# Light_node.net
KiCad netlist of a schematic drawn in EAGLE
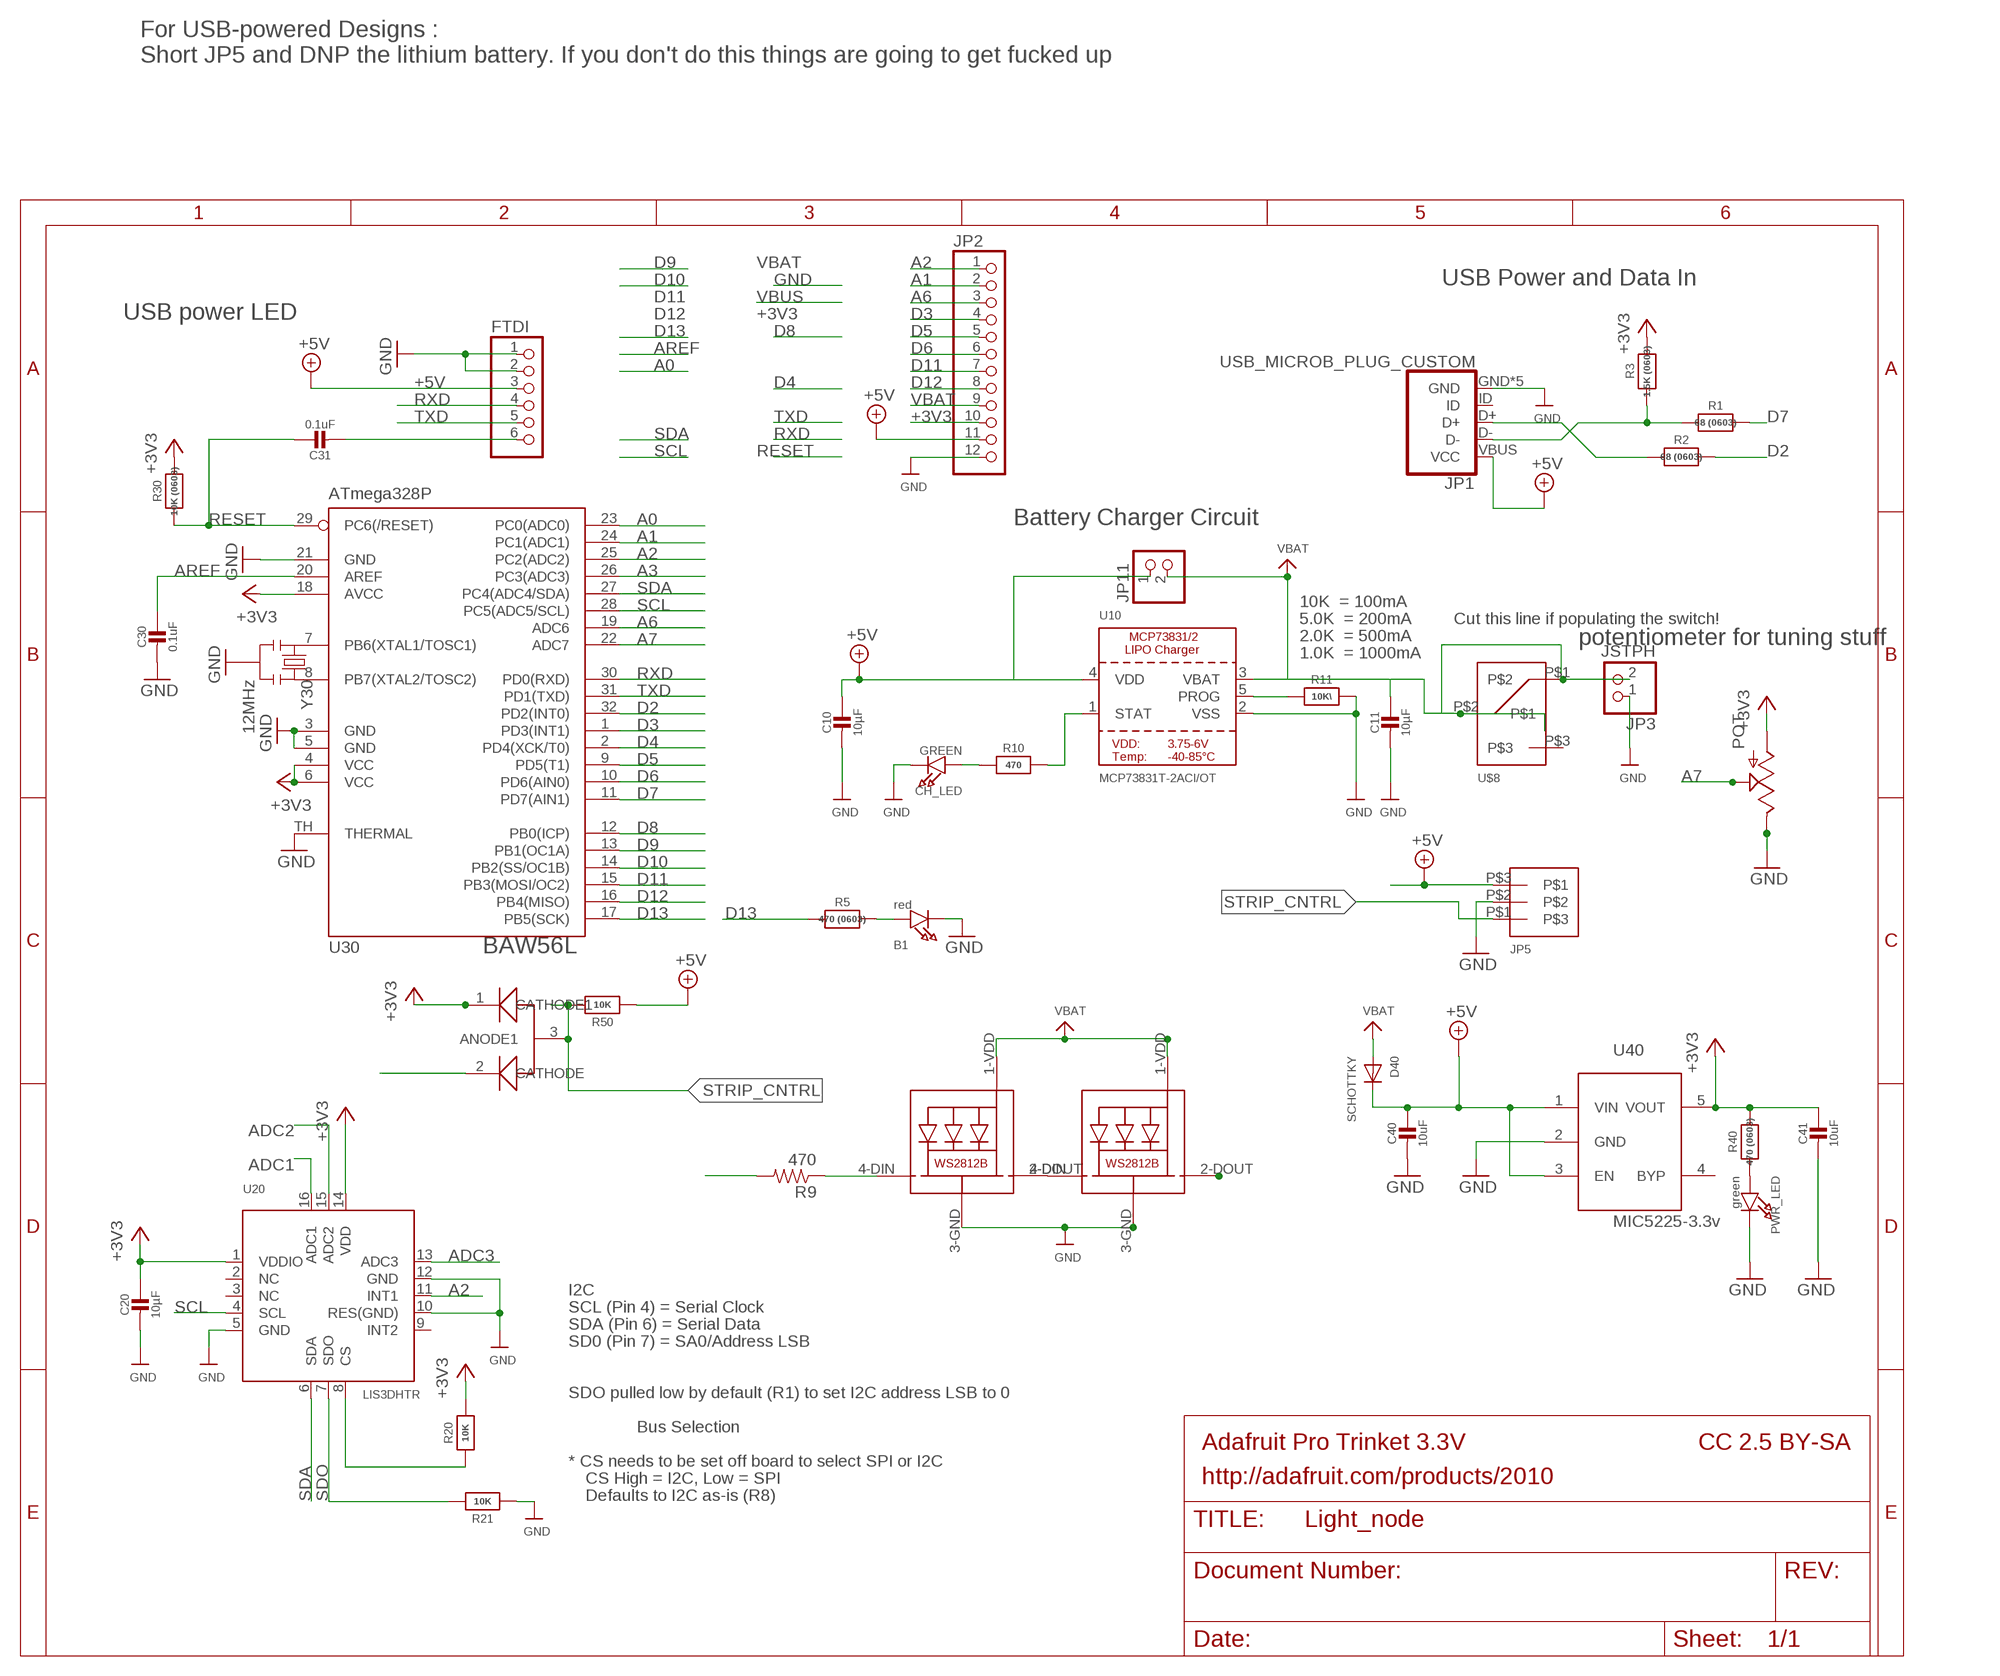
[diagram p0: schematic, sheet 1]

(export (version "E")
  (design (tool "Eeschema 10.0.6"))
  (components
    (comp (ref "B1")
      (value "red")
      (footprint "eagle-import:CHIPLED_0805_NOOUTLINE")
      (libsource (lib "eagle-import") (part "LED0805_NOOUTLINE"))
    )
    (comp (ref "C10")
      (value "10µF")
      (footprint "eagle-import:0805-NO")
      (libsource (lib "eagle-import") (part "CAP_CERAMIC0805-NOOUTLINE"))
    )
    (comp (ref "C11")
      (value "10µF")
      (footprint "eagle-import:0805-NO")
      (libsource (lib "eagle-import") (part "CAP_CERAMIC0805-NOOUTLINE"))
    )
    (comp (ref "C20")
      (value "10µF")
      (footprint "eagle-import:0805-NO")
      (libsource (lib "eagle-import") (part "CAP_CERAMIC0805-NOOUTLINE"))
    )
    (comp (ref "C30")
      (value "0.1uF")
      (footprint "eagle-import:_0805MP")
      (libsource (lib "eagle-import") (part "CAP_CERAMIC_0805MP"))
    )
    (comp (ref "C31")
      (value "0.1uF")
      (footprint "eagle-import:0805-NO")
      (libsource (lib "eagle-import") (part "CAP_CERAMIC0805-NOOUTLINE"))
    )
    (comp (ref "C40")
      (value "10uF")
      (footprint "eagle-import:0805-NO")
      (libsource (lib "eagle-import") (part "CAP_CERAMIC0805-NOOUTLINE"))
    )
    (comp (ref "C41")
      (value "10uF")
      (footprint "eagle-import:0805-NO")
      (libsource (lib "eagle-import") (part "CAP_CERAMIC0805-NOOUTLINE"))
    )
    (comp (ref "CH_LED")
      (value "GREEN")
      (footprint "eagle-import:CHIPLED_0805_NOOUTLINE")
      (libsource (lib "eagle-import") (part "LED0805_NOOUTLINE"))
    )
    (comp (ref "D40")
      (value "SCHOTTKY")
      (footprint "eagle-import:SOD-123FL")
      (libsource (lib "eagle-import") (part "DIODE_SOD-123FL"))
    )
    (comp (ref "FTDI")
      (value "PINHD-1X6CB")
      (footprint "eagle-import:1X06-CLEANBIG")
      (libsource (lib "eagle-import") (part "PINHD-1X6CB"))
    )
    (comp (ref "JP1")
      (value "USB_MICROB_PLUG_CUSTOM")
      (footprint "eagle-import:USB-MICROB")
      (libsource (lib "eagle-import") (part "USB_MICROB_PLUG_CUSTOM"))
    )
    (comp (ref "JP2")
      (value "PINHD-1X12-CB")
      (footprint "eagle-import:1X12-CB")
      (libsource (lib "eagle-import") (part "PINHD-1X12-CB"))
    )
    (comp (ref "JP3")
      (value "JSTPH")
      (footprint "eagle-import:JSTPH2")
      (libsource (lib "eagle-import") (part "JST_2PIN"))
    )
    (comp (ref "JP5")
      (value "M03")
      (footprint "eagle-import:M03_25MM")
      (libsource (lib "eagle-import") (part "M03"))
    )
    (comp (ref "JP11")
      (value "HEADER-1X2ROUND")
      (footprint "eagle-import:1X02_ROUND")
      (libsource (lib "eagle-import") (part "HEADER-1X2ROUND"))
    )
    (comp (ref "POT")
      (value "POT")
      (footprint "eagle-import:3306P_POT")
      (libsource (lib "eagle-import") (part "POT"))
    )
    (comp (ref "PWR_LED")
      (value "green")
      (footprint "eagle-import:CHIPLED_0805_NOOUTLINE")
      (libsource (lib "eagle-import") (part "LED0805_NOOUTLINE"))
    )
    (comp (ref "R1")
      (value "68 (0603)")
      (footprint "eagle-import:0603-NO")
      (libsource (lib "eagle-import") (part "RESISTOR_0603_NOOUT"))
    )
    (comp (ref "R2")
      (value "68 (0603)")
      (footprint "eagle-import:0603-NO")
      (libsource (lib "eagle-import") (part "RESISTOR_0603_NOOUT"))
    )
    (comp (ref "R3")
      (value "1.5K (0603)")
      (footprint "eagle-import:0603-NO")
      (libsource (lib "eagle-import") (part "RESISTOR_0603_NOOUT"))
    )
    (comp (ref "R5")
      (value "470 (0603)")
      (footprint "eagle-import:0603-NO")
      (libsource (lib "eagle-import") (part "RESISTOR_0603_NOOUT"))
    )
    (comp (ref "R9")
      (value "470")
      (footprint "eagle-import:0603-RES")
      (libsource (lib "eagle-import") (part "RESISTOR0603-RES"))
    )
    (comp (ref "R10")
      (value "470")
      (footprint "eagle-import:0805-NO")
      (libsource (lib "eagle-import") (part "RESISTOR0805_NOOUTLINE"))
    )
    (comp (ref "R11")
      (value "10K\\")
      (footprint "eagle-import:0805-NO")
      (libsource (lib "eagle-import") (part "RESISTOR0805_NOOUTLINE"))
    )
    (comp (ref "R20")
      (value "10K")
      (footprint "eagle-import:0805-NO")
      (libsource (lib "eagle-import") (part "RESISTOR0805_NOOUTLINE"))
    )
    (comp (ref "R21")
      (value "10K")
      (footprint "eagle-import:0805-NO")
      (libsource (lib "eagle-import") (part "RESISTOR0805_NOOUTLINE"))
    )
    (comp (ref "R30")
      (value "10K (0603)")
      (footprint "eagle-import:0805-NO")
      (libsource (lib "eagle-import") (part "RESISTOR0805_NOOUTLINE"))
    )
    (comp (ref "R40")
      (value "470 (0603)")
      (footprint "eagle-import:0603-NO")
      (libsource (lib "eagle-import") (part "RESISTOR_0603_NOOUT"))
    )
    (comp (ref "R50")
      (value "10K")
      (footprint "eagle-import:0603-NO")
      (libsource (lib "eagle-import") (part "RESISTOR_0603_NOOUT"))
    )
    (comp (ref "RGB1")
      (value "WS2812B5050")
      (footprint "eagle-import:WS2812B")
      (libsource (lib "eagle-import") (part "WS2812B5050"))
    )
    (comp (ref "RGB2")
      (value "WS2812B5050")
      (footprint "eagle-import:WS2812B")
      (libsource (lib "eagle-import") (part "WS2812B5050"))
    )
    (comp (ref "U$8")
      (value "SPDT_NO_GNDSMT")
      (footprint "eagle-import:JS102011SAQN")
      (libsource (lib "eagle-import") (part "SPDT_NO_GNDSMT"))
    )
    (comp (ref "U10")
      (value "MCP73831T-2ACI/OT")
      (footprint "eagle-import:SOT23-5")
      (libsource (lib "eagle-import") (part "MCP73831/2"))
    )
    (comp (ref "U20")
      (value "LIS3DHTR")
      (footprint "eagle-import:LGA16_3X3MM")
      (libsource (lib "eagle-import") (part "ACCEL_LIS3DHTR"))
    )
    (comp (ref "U30")
      (value "ATmega328P")
      (footprint "eagle-import:MLF32-TH")
      (fields (field (name "MPN") "ATMEGA88PA-MU"))
      (libsource (lib "eagle-import") (part "MEGA8-MI"))
    )
    (comp (ref "U40")
      (value "MIC5225-3.3v")
      (footprint "eagle-import:SOT23-5L")
      (libsource (lib "eagle-import") (part "LP298XS"))
    )
    (comp (ref "U50")
      (value "COMMON_ANODE_DIODE")
      (footprint "eagle-import:SOT23")
      (libsource (lib "eagle-import") (part "COMMON_ANODE_DIODE"))
    )
    (comp (ref "Y30")
      (value "12MHz")
      (footprint "eagle-import:RESONATOR-SMD")
      (libsource (lib "eagle-import") (part "RESONATORSMD"))
    )
  )
  (nets
    (net (code "1") (name "+3V3") (class "Default")
      (node (ref "C20") (pin "1") (pinfunction "1_1") (pintype "passive"))
      (node (ref "C41") (pin "1") (pinfunction "1_1") (pintype "passive"))
      (node (ref "JP2") (pin "10") (pinfunction "10_10") (pintype "passive"))
      (node (ref "POT") (pin "P$1") (pinfunction "A_P$1") (pintype "passive"))
      (node (ref "R20") (pin "2") (pinfunction "2_2") (pintype "passive"))
      (node (ref "R3") (pin "2") (pinfunction "2_2") (pintype "passive"))
      (node (ref "R30") (pin "2") (pinfunction "2_2") (pintype "passive"))
      (node (ref "R40") (pin "2") (pinfunction "2_2") (pintype "passive"))
      (node (ref "U20") (pin "1") (pinfunction "VDDIO_1") (pintype "power_in"))
      (node (ref "U20") (pin "14") (pinfunction "VDD_14") (pintype "power_in"))
      (node (ref "U30") (pin "18") (pinfunction "AVCC_18") (pintype "power_in"))
      (node (ref "U30") (pin "4") (pinfunction "VCC_4") (pintype "power_in"))
      (node (ref "U30") (pin "6") (pinfunction "VCC_6") (pintype "power_in"))
      (node (ref "U40") (pin "5") (pinfunction "VOUT_5") (pintype "bidirectional"))
      (node (ref "U50") (pin "1") (pinfunction "CATHODE1_1") (pintype "bidirectional"))
    )
    (net (code "2") (name "+5V") (class "Default")
      (node (ref "C10") (pin "1") (pinfunction "1_1") (pintype "passive"))
      (node (ref "C40") (pin "1") (pinfunction "1_1") (pintype "passive"))
      (node (ref "D40") (pin "C") (pinfunction "C_C") (pintype "passive"))
      (node (ref "FTDI") (pin "3") (pinfunction "3_3") (pintype "passive"))
      (node (ref "JP1") (pin "VBUS") (pinfunction "VCC_VBUS") (pintype "bidirectional"))
      (node (ref "JP11") (pin "1") (pinfunction "1_1") (pintype "passive"))
      (node (ref "JP2") (pin "11") (pinfunction "11_11") (pintype "passive"))
      (node (ref "JP5") (pin "P$3") (pinfunction "P$1_P$3") (pintype "bidirectional"))
      (node (ref "R50") (pin "1") (pinfunction "1_1") (pintype "passive"))
      (node (ref "U10") (pin "4") (pinfunction "VDD_4") (pintype "power_in"))
      (node (ref "U40") (pin "1") (pinfunction "VIN_1") (pintype "bidirectional"))
      (node (ref "U40") (pin "3") (pinfunction "EN_3") (pintype "bidirectional"))
    )
    (net (code "3") (name "/A0") (class "Default")
      (node (ref "U30") (pin "23") (pinfunction "PC0(ADC0)_23") (pintype "bidirectional"))
    )
    (net (code "4") (name "/A1") (class "Default")
      (node (ref "JP2") (pin "2") (pinfunction "2_2") (pintype "passive"))
      (node (ref "U30") (pin "24") (pinfunction "PC1(ADC1)_24") (pintype "bidirectional"))
    )
    (net (code "5") (name "/A2") (class "Default")
      (node (ref "JP2") (pin "1") (pinfunction "1_1") (pintype "passive"))
      (node (ref "U20") (pin "11") (pinfunction "INT1_11") (pintype "output"))
      (node (ref "U30") (pin "25") (pinfunction "PC2(ADC2)_25") (pintype "bidirectional"))
    )
    (net (code "6") (name "/A3") (class "Default")
      (node (ref "U30") (pin "26") (pinfunction "PC3(ADC3)_26") (pintype "bidirectional"))
    )
    (net (code "7") (name "/A6") (class "Default")
      (node (ref "JP2") (pin "3") (pinfunction "3_3") (pintype "passive"))
      (node (ref "U30") (pin "19") (pinfunction "ADC6_19") (pintype "bidirectional"))
    )
    (net (code "8") (name "/A7") (class "Default")
      (node (ref "POT") (pin "P$3") (pinfunction "S_P$3") (pintype "passive"))
      (node (ref "U30") (pin "22") (pinfunction "ADC7_22") (pintype "bidirectional"))
    )
    (net (code "9") (name "/ADC1") (class "Default")
      (node (ref "U20") (pin "16") (pinfunction "ADC1_16") (pintype "input"))
    )
    (net (code "10") (name "/ADC2") (class "Default")
      (node (ref "U20") (pin "15") (pinfunction "ADC2_15") (pintype "input"))
    )
    (net (code "11") (name "/ADC3") (class "Default")
      (node (ref "U20") (pin "13") (pinfunction "ADC3_13") (pintype "input"))
    )
    (net (code "12") (name "/AREF") (class "Default")
      (node (ref "C30") (pin "1") (pinfunction "1_1") (pintype "passive"))
      (node (ref "U30") (pin "20") (pinfunction "AREF_20") (pintype "passive"))
    )
    (net (code "13") (name "/D2") (class "Default")
      (node (ref "R2") (pin "2") (pinfunction "2_2") (pintype "passive"))
      (node (ref "U30") (pin "32") (pinfunction "PD2(INT0)_32") (pintype "bidirectional"))
    )
    (net (code "14") (name "/D3") (class "Default")
      (node (ref "JP2") (pin "4") (pinfunction "4_4") (pintype "passive"))
      (node (ref "U30") (pin "1") (pinfunction "PD3(INT1)_1") (pintype "bidirectional"))
    )
    (net (code "15") (name "/D4") (class "Default")
      (node (ref "U30") (pin "2") (pinfunction "PD4(XCK/T0)_2") (pintype "bidirectional"))
      (node (ref "U50") (pin "2") (pinfunction "CATHODE_2") (pintype "bidirectional"))
    )
    (net (code "16") (name "/D5") (class "Default")
      (node (ref "JP2") (pin "5") (pinfunction "5_5") (pintype "passive"))
      (node (ref "U30") (pin "9") (pinfunction "PD5(T1)_9") (pintype "bidirectional"))
    )
    (net (code "17") (name "/D6") (class "Default")
      (node (ref "JP2") (pin "6") (pinfunction "6_6") (pintype "passive"))
      (node (ref "U30") (pin "10") (pinfunction "PD6(AIN0)_10") (pintype "bidirectional"))
    )
    (net (code "18") (name "/D7") (class "Default")
      (node (ref "R1") (pin "2") (pinfunction "2_2") (pintype "passive"))
      (node (ref "U30") (pin "11") (pinfunction "PD7(AIN1)_11") (pintype "bidirectional"))
    )
    (net (code "19") (name "/D8") (class "Default")
      (node (ref "U30") (pin "12") (pinfunction "PB0(ICP)_12") (pintype "bidirectional"))
    )
    (net (code "20") (name "/D9") (class "Default")
      (node (ref "U30") (pin "13") (pinfunction "PB1(OC1A)_13") (pintype "bidirectional"))
    )
    (net (code "21") (name "/D10") (class "Default")
      (node (ref "R9") (pin "2") (pinfunction "2_2") (pintype "passive"))
      (node (ref "U30") (pin "14") (pinfunction "PB2(SS/OC1B)_14") (pintype "bidirectional"))
    )
    (net (code "22") (name "/D11") (class "Default")
      (node (ref "JP2") (pin "7") (pinfunction "7_7") (pintype "passive"))
      (node (ref "U30") (pin "15") (pinfunction "PB3(MOSI/OC2)_15") (pintype "bidirectional"))
    )
    (net (code "23") (name "/D12") (class "Default")
      (node (ref "JP2") (pin "8") (pinfunction "8_8") (pintype "passive"))
      (node (ref "U30") (pin "16") (pinfunction "PB4(MISO)_16") (pintype "bidirectional"))
    )
    (net (code "24") (name "/D13") (class "Default")
      (node (ref "R5") (pin "2") (pinfunction "2_2") (pintype "passive"))
      (node (ref "U30") (pin "17") (pinfunction "PB5(SCK)_17") (pintype "bidirectional"))
    )
    (net (code "25") (name "/RESET") (class "Default")
      (node (ref "C31") (pin "1") (pinfunction "1_1") (pintype "passive"))
      (node (ref "R30") (pin "1") (pinfunction "1_1") (pintype "passive"))
      (node (ref "U30") (pin "29") (pinfunction "PC6(/RESET)_29") (pintype "bidirectional"))
    )
    (net (code "26") (name "/RXD") (class "Default")
      (node (ref "FTDI") (pin "4") (pinfunction "4_4") (pintype "passive"))
      (node (ref "U30") (pin "30") (pinfunction "PD0(RXD)_30") (pintype "bidirectional"))
    )
    (net (code "27") (name "/SCL") (class "Default")
      (node (ref "U20") (pin "4") (pinfunction "SCL_4") (pintype "bidirectional"))
      (node (ref "U30") (pin "28") (pinfunction "PC5(ADC5/SCL)_28") (pintype "bidirectional"))
    )
    (net (code "28") (name "/SDA") (class "Default")
      (node (ref "U20") (pin "6") (pinfunction "SDA_6") (pintype "bidirectional"))
      (node (ref "U30") (pin "27") (pinfunction "PC4(ADC4/SDA)_27") (pintype "bidirectional"))
    )
    (net (code "29") (name "/SDO") (class "Default")
      (node (ref "R21") (pin "2") (pinfunction "2_2") (pintype "passive"))
      (node (ref "U20") (pin "7") (pinfunction "SDO_7") (pintype "bidirectional"))
    )
    (net (code "30") (name "/TXD") (class "Default")
      (node (ref "FTDI") (pin "5") (pinfunction "5_5") (pintype "passive"))
      (node (ref "U30") (pin "31") (pinfunction "PD1(TXD)_31") (pintype "bidirectional"))
    )
    (net (code "32") (name "GND") (class "Default")
      (node (ref "B1") (pin "C") (pinfunction "C_C") (pintype "passive"))
      (node (ref "C10") (pin "2") (pinfunction "2_2") (pintype "passive"))
      (node (ref "C11") (pin "2") (pinfunction "2_2") (pintype "passive"))
      (node (ref "C20") (pin "2") (pinfunction "2_2") (pintype "passive"))
      (node (ref "C30") (pin "2") (pinfunction "2_2") (pintype "passive"))
      (node (ref "C40") (pin "2") (pinfunction "2_2") (pintype "passive"))
      (node (ref "C41") (pin "2") (pinfunction "2_2") (pintype "passive"))
      (node (ref "CH_LED") (pin "C") (pinfunction "C_C") (pintype "passive"))
      (node (ref "FTDI") (pin "1") (pinfunction "1_1") (pintype "passive"))
      (node (ref "FTDI") (pin "2") (pinfunction "2_2") (pintype "passive"))
      (node (ref "JP1") (pin "GND") (pinfunction "GND_GND") (pintype "bidirectional"))
      (node (ref "JP1") (pin "P$1") (pinfunction "GND_P$1") (pintype "bidirectional"))
      (node (ref "JP1") (pin "P$2") (pinfunction "GND_P$2") (pintype "bidirectional"))
      (node (ref "JP1") (pin "P$3") (pinfunction "GND_P$3") (pintype "bidirectional"))
      (node (ref "JP1") (pin "P$4") (pinfunction "GND_P$4") (pintype "bidirectional"))
      (node (ref "JP2") (pin "12") (pinfunction "12_12") (pintype "passive"))
      (node (ref "JP3") (pin "1") (pinfunction "1_1") (pintype "passive"))
      (node (ref "JP5") (pin "P$2") (pinfunction "P$2_P$2") (pintype "bidirectional"))
      (node (ref "POT") (pin "P$2") (pinfunction "E_P$2") (pintype "passive"))
      (node (ref "PWR_LED") (pin "C") (pinfunction "C_C") (pintype "passive"))
      (node (ref "R11") (pin "2") (pinfunction "2_2") (pintype "passive"))
      (node (ref "R21") (pin "1") (pinfunction "1_1") (pintype "passive"))
      (node (ref "RGB1") (pin "3-GND") (pinfunction "GND_3-GND") (pintype "power_in"))
      (node (ref "RGB2") (pin "3-GND") (pinfunction "GND_3-GND") (pintype "power_in"))
      (node (ref "U10") (pin "2") (pinfunction "VSS_2") (pintype "power_in"))
      (node (ref "U20") (pin "10") (pinfunction "RES(GND)_10") (pintype "bidirectional"))
      (node (ref "U20") (pin "12") (pinfunction "GND_12") (pintype "power_in"))
      (node (ref "U20") (pin "5") (pinfunction "GND_5") (pintype "power_in"))
      (node (ref "U30") (pin "21") (pinfunction "GND_21") (pintype "power_in"))
      (node (ref "U30") (pin "3") (pinfunction "GND_3") (pintype "power_in"))
      (node (ref "U30") (pin "5") (pinfunction "GND_5") (pintype "power_in"))
      (node (ref "U30") (pin "TH") (pinfunction "THERMAL_TH") (pintype "passive"))
      (node (ref "U40") (pin "2") (pinfunction "GND_2") (pintype "bidirectional"))
      (node (ref "Y30") (pin "2") (pinfunction "2_2") (pintype "passive"))
    )
    (net (code "33") (name "Net-(B1-PadA)") (class "Default")
      (node (ref "B1") (pin "A") (pinfunction "A_A") (pintype "passive"))
      (node (ref "R5") (pin "1") (pinfunction "1_1") (pintype "passive"))
    )
    (net (code "34") (name "Net-(C31-Pad2)") (class "Default")
      (node (ref "C31") (pin "2") (pinfunction "2_2") (pintype "passive"))
      (node (ref "FTDI") (pin "6") (pinfunction "6_6") (pintype "passive"))
    )
    (net (code "35") (name "Net-(CH_LED-PadA)") (class "Default")
      (node (ref "CH_LED") (pin "A") (pinfunction "A_A") (pintype "passive"))
      (node (ref "R10") (pin "1") (pinfunction "1_1") (pintype "passive"))
    )
    (net (code "36") (name "Net-(JP1-PadD+)") (class "Default")
      (node (ref "JP1") (pin "D+") (pinfunction "D+_D+") (pintype "bidirectional"))
      (node (ref "R2") (pin "1") (pinfunction "1_1") (pintype "passive"))
    )
    (net (code "37") (name "Net-(JP1-PadD-)") (class "Default")
      (node (ref "JP1") (pin "D-") (pinfunction "D-_D-") (pintype "bidirectional"))
      (node (ref "R1") (pin "1") (pinfunction "1_1") (pintype "passive"))
      (node (ref "R3") (pin "1") (pinfunction "1_1") (pintype "passive"))
    )
    (net (code "38") (name "Net-(PWR_LED-PadA)") (class "Default")
      (node (ref "PWR_LED") (pin "A") (pinfunction "A_A") (pintype "passive"))
      (node (ref "R40") (pin "1") (pinfunction "1_1") (pintype "passive"))
    )
    (net (code "39") (name "Net-(RGB1-DI)") (class "Default")
      (node (ref "R9") (pin "1") (pinfunction "1_1") (pintype "passive"))
      (node (ref "RGB1") (pin "4-DIN") (pinfunction "DI_4-DIN") (pintype "input"))
    )
    (net (code "40") (name "Net-(RGB1-DO)") (class "Default")
      (node (ref "RGB1") (pin "2-DOUT") (pinfunction "DO_2-DOUT") (pintype "output"))
      (node (ref "RGB2") (pin "4-DIN") (pinfunction "DI_4-DIN") (pintype "input"))
    )
    (net (code "41") (name "Net-(U10-PROG)") (class "Default")
      (node (ref "R11") (pin "1") (pinfunction "1_1") (pintype "passive"))
      (node (ref "U10") (pin "5") (pinfunction "PROG_5") (pintype "input"))
    )
    (net (code "42") (name "Net-(U10-STAT)") (class "Default")
      (node (ref "R10") (pin "2") (pinfunction "2_2") (pintype "passive"))
      (node (ref "U10") (pin "1") (pinfunction "STAT_1") (pintype "output"))
    )
    (net (code "43") (name "Net-(U20-CS)") (class "Default")
      (node (ref "R20") (pin "1") (pinfunction "1_1") (pintype "passive"))
      (node (ref "U20") (pin "8") (pinfunction "CS_8") (pintype "input"))
    )
    (net (code "44") (name "Net-(U30-PB6(XTAL1{slash}TOSC1))") (class "Default")
      (node (ref "U30") (pin "7") (pinfunction "PB6(XTAL1/TOSC1)_7") (pintype "bidirectional"))
      (node (ref "Y30") (pin "1") (pinfunction "1_1") (pintype "passive"))
    )
    (net (code "45") (name "Net-(U30-PB7(XTAL2{slash}TOSC2))") (class "Default")
      (node (ref "U30") (pin "8") (pinfunction "PB7(XTAL2/TOSC2)_8") (pintype "bidirectional"))
      (node (ref "Y30") (pin "3") (pinfunction "3_3") (pintype "passive"))
    )
    (net (code "46") (name "STRIP_CNTRL") (class "Default")
      (node (ref "JP5") (pin "P$1") (pinfunction "P$3_P$1") (pintype "bidirectional"))
      (node (ref "R50") (pin "2") (pinfunction "2_2") (pintype "passive"))
      (node (ref "U50") (pin "3") (pinfunction "ANODE1_3") (pintype "bidirectional"))
    )
    (net (code "47") (name "VBAT") (class "Default")
      (node (ref "C11") (pin "1") (pinfunction "1_1") (pintype "passive"))
      (node (ref "D40") (pin "A") (pinfunction "A_A") (pintype "passive"))
      (node (ref "JP11") (pin "2") (pinfunction "2_2") (pintype "passive"))
      (node (ref "JP2") (pin "9") (pinfunction "9_9") (pintype "passive"))
      (node (ref "JP3") (pin "2") (pinfunction "2_2") (pintype "passive"))
      (node (ref "RGB1") (pin "1-VDD") (pinfunction "VDD_1-VDD") (pintype "power_in"))
      (node (ref "RGB2") (pin "1-VDD") (pinfunction "VDD_1-VDD") (pintype "power_in"))
      (node (ref "U$8") (pin "P$1") (pinfunction "P$2_P$1") (pintype "bidirectional"))
      (node (ref "U$8") (pin "P$2") (pinfunction "P$1_P$2") (pintype "bidirectional"))
      (node (ref "U10") (pin "3") (pinfunction "VBAT_3") (pintype "power_in"))
    )
    (net (code "48") (name "unconnected-(JP1-PadID)") (class "Default")
      (node (ref "JP1") (pin "ID") (pinfunction "ID_ID") (pintype "bidirectional"))
    )
    (net (code "49") (name "unconnected-(RGB2-DO-Pad2-DOUT)") (class "Default")
      (node (ref "RGB2") (pin "2-DOUT") (pinfunction "DO_2-DOUT") (pintype "output"))
    )
    (net (code "50") (name "unconnected-(U$8-PadP$3)") (class "Default")
      (node (ref "U$8") (pin "P$3") (pinfunction "P$3_P$3") (pintype "bidirectional"))
    )
    (net (code "51") (name "unconnected-(U20-INT2-Pad9)") (class "Default")
      (node (ref "U20") (pin "9") (pinfunction "INT2_9") (pintype "output"))
    )
    (net (code "52") (name "unconnected-(U20-NC-Pad2)") (class "Default")
      (node (ref "U20") (pin "2") (pinfunction "NC_2") (pintype "no_connect"))
    )
    (net (code "53") (name "unconnected-(U20-NC-Pad3)") (class "Default")
      (node (ref "U20") (pin "3") (pinfunction "NC_3") (pintype "no_connect"))
    )
    (net (code "54") (name "unconnected-(U40-BYP-Pad4)") (class "Default")
      (node (ref "U40") (pin "4") (pinfunction "BYP_4") (pintype "bidirectional"))
    )
  )
)
